# skematikEasyEDA.net
KiCad netlist of a schematic drawn in EasyEDA
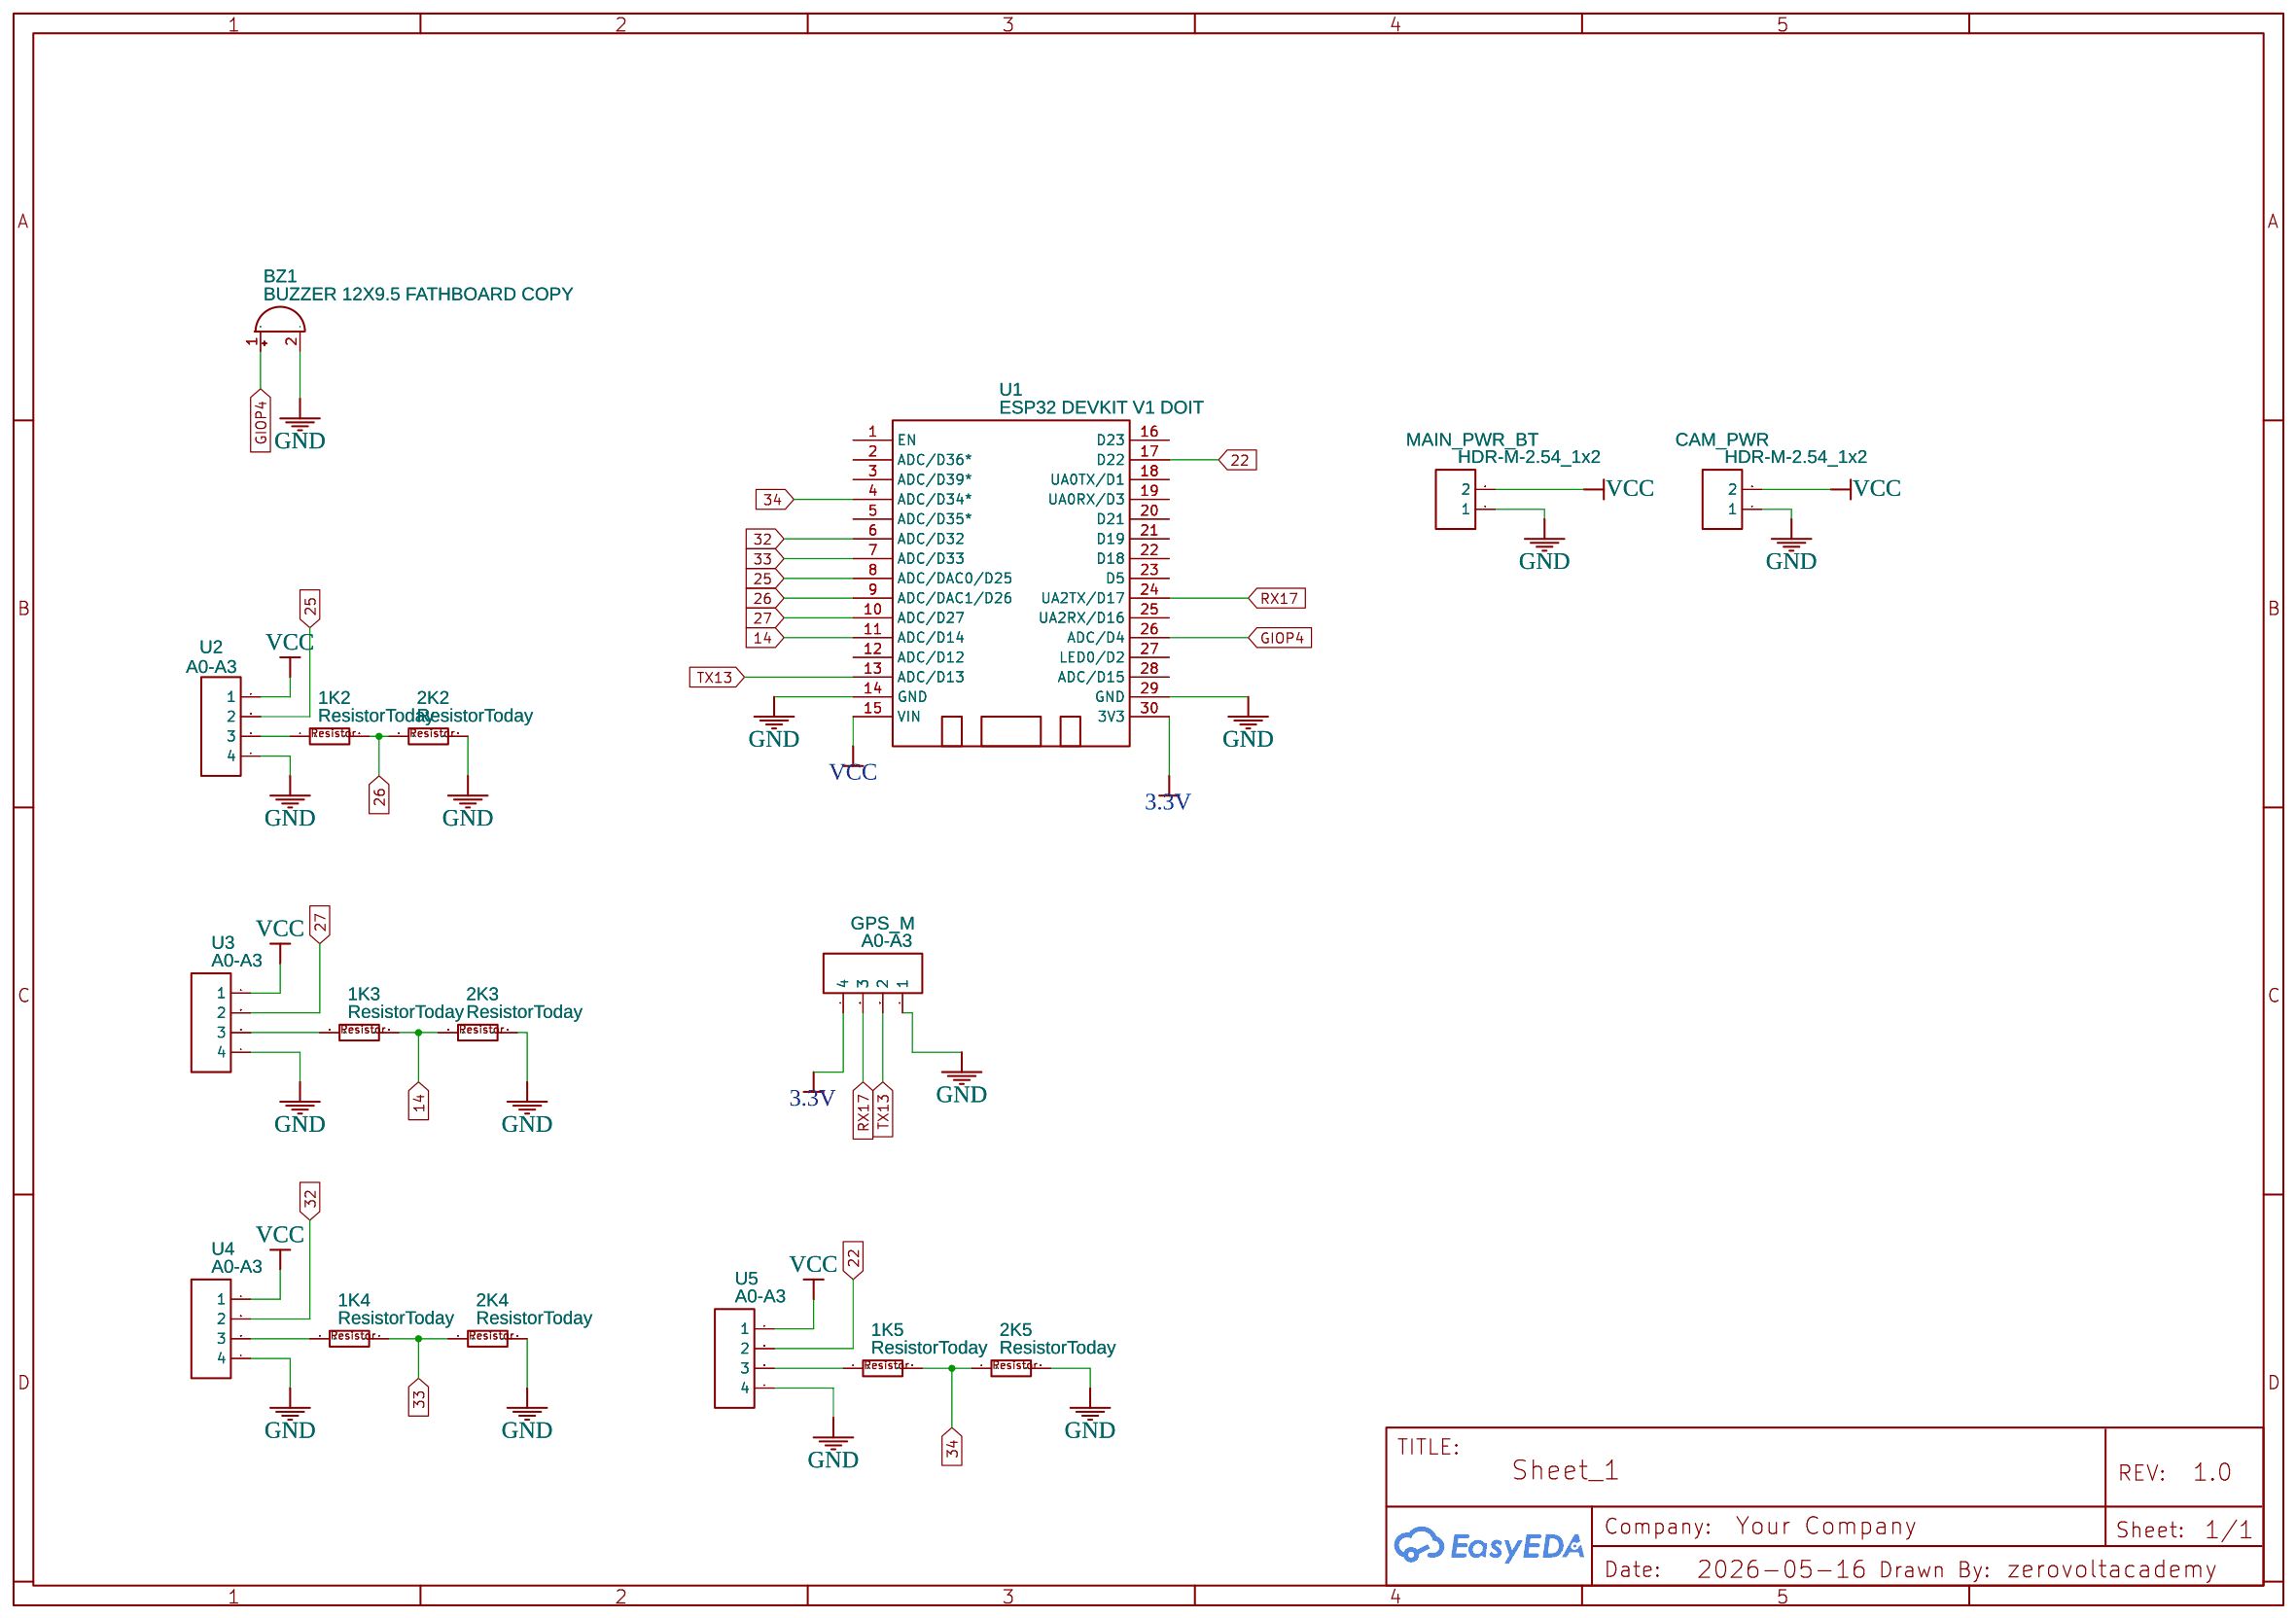
[diagram p0: schematic sheet]

(export (version "E")
  (design (tool "Eeschema 10.0.6"))
  (components
    (comp (ref "1K2")
      (value "ResistorToday")
      (fields (field (name "Manufacturer Part") "EWWR0001J20R0T9"))
      (libsource (lib "") (part "RESISTOR COPY_1"))
    )
    (comp (ref "1K3")
      (value "ResistorToday")
      (fields (field (name "Manufacturer Part") "EWWR0001J20R0T9"))
      (libsource (lib "") (part "RESISTOR COPY_1"))
    )
    (comp (ref "1K4")
      (value "ResistorToday")
      (fields (field (name "Manufacturer Part") "EWWR0001J20R0T9"))
      (libsource (lib "") (part "RESISTOR COPY_1"))
    )
    (comp (ref "1K5")
      (value "ResistorToday")
      (fields (field (name "Manufacturer Part") "EWWR0001J20R0T9"))
      (libsource (lib "") (part "RESISTOR COPY_1"))
    )
    (comp (ref "2K2")
      (value "ResistorToday")
      (fields (field (name "Manufacturer Part") "EWWR0001J20R0T9"))
      (libsource (lib "") (part "RESISTOR COPY"))
    )
    (comp (ref "2K3")
      (value "ResistorToday")
      (fields (field (name "Manufacturer Part") "EWWR0001J20R0T9"))
      (libsource (lib "") (part "RESISTOR COPY"))
    )
    (comp (ref "2K4")
      (value "ResistorToday")
      (fields (field (name "Manufacturer Part") "EWWR0001J20R0T9"))
      (libsource (lib "") (part "RESISTOR COPY"))
    )
    (comp (ref "2K5")
      (value "ResistorToday")
      (fields (field (name "Manufacturer Part") "EWWR0001J20R0T9"))
      (libsource (lib "") (part "RESISTOR COPY"))
    )
    (comp (ref "BZ1")
      (value "BUZZER 12X9.5 FATHBOARD COPY")
      (libsource (lib "") (part "BUZZER 12X9.5 FATHBOARD COPY"))
    )
    (comp (ref "CAM_PWR") (value "HDR-M-2.54_1x2") (libsource (lib "") (part "HDR-M-2.54_1x2_1")))
    (comp (ref "GPS_M")
      (value "A0-A3")
      (fields
        (field (name "Manufacturer Part") "Female headerHDR1X8-2.54")
        (field (name "Manufacturer") "BOOMELE")
      )
      (libsource (lib "") (part "HEADER PAD 2X_1"))
    )
    (comp (ref "MAIN_PWR_BT") (value "HDR-M-2.54_1x2") (libsource (lib "") (part "HDR-M-2.54_1x2")))
    (comp (ref "U1") (value "ESP32 DEVKIT V1 DOIT") (libsource (lib "") (part "ESP32 DEVKIT V1 DOIT")))
    (comp (ref "U2")
      (value "A0-A3")
      (fields
        (field (name "Manufacturer Part") "Female headerHDR1X8-2.54")
        (field (name "Manufacturer") "BOOMELE")
      )
      (libsource (lib "") (part "HEADER PAD 2X"))
    )
    (comp (ref "U3")
      (value "A0-A3")
      (fields
        (field (name "Manufacturer Part") "Female headerHDR1X8-2.54")
        (field (name "Manufacturer") "BOOMELE")
      )
      (libsource (lib "") (part "HEADER PAD 2X"))
    )
    (comp (ref "U4")
      (value "A0-A3")
      (fields
        (field (name "Manufacturer Part") "Female headerHDR1X8-2.54")
        (field (name "Manufacturer") "BOOMELE")
      )
      (libsource (lib "") (part "HEADER PAD 2X"))
    )
    (comp (ref "U5")
      (value "A0-A3")
      (fields
        (field (name "Manufacturer Part") "Female headerHDR1X8-2.54")
        (field (name "Manufacturer") "BOOMELE")
      )
      (libsource (lib "") (part "HEADER PAD 2X"))
    )
  )
  (nets
    (net (code "1") (name "3.3V") (class "Default")
      (node (ref "GPS_M") (pin "4") (pinfunction "4_4") (pintype "unspecified"))
      (node (ref "U1") (pin "30") (pinfunction "3V3_30") (pintype "bidirectional"))
    )
    (net (code "2") (name "14") (class "Default")
      (node (ref "1K3") (pin "2") (pinfunction "2_2") (pintype "unspecified"))
      (node (ref "2K3") (pin "1") (pinfunction "1_1") (pintype "unspecified"))
      (node (ref "U1") (pin "11") (pinfunction "ADC/D14_11") (pintype "bidirectional"))
    )
    (net (code "3") (name "22") (class "Default")
      (node (ref "U1") (pin "17") (pinfunction "D22_17") (pintype "bidirectional"))
      (node (ref "U5") (pin "2") (pinfunction "2_2") (pintype "unspecified"))
    )
    (net (code "4") (name "25") (class "Default")
      (node (ref "U1") (pin "8") (pinfunction "ADC/DAC0/D25_8") (pintype "bidirectional"))
      (node (ref "U2") (pin "2") (pinfunction "2_2") (pintype "unspecified"))
    )
    (net (code "5") (name "26") (class "Default")
      (node (ref "1K2") (pin "2") (pinfunction "2_2") (pintype "unspecified"))
      (node (ref "2K2") (pin "1") (pinfunction "1_1") (pintype "unspecified"))
      (node (ref "U1") (pin "9") (pinfunction "ADC/DAC1/D26_9") (pintype "bidirectional"))
    )
    (net (code "6") (name "27") (class "Default")
      (node (ref "U1") (pin "10") (pinfunction "ADC/D27_10") (pintype "bidirectional"))
      (node (ref "U3") (pin "2") (pinfunction "2_2") (pintype "unspecified"))
    )
    (net (code "7") (name "32") (class "Default")
      (node (ref "U1") (pin "6") (pinfunction "ADC/D32_6") (pintype "bidirectional"))
      (node (ref "U4") (pin "2") (pinfunction "2_2") (pintype "unspecified"))
    )
    (net (code "8") (name "33") (class "Default")
      (node (ref "1K4") (pin "2") (pinfunction "2_2") (pintype "unspecified"))
      (node (ref "2K4") (pin "1") (pinfunction "1_1") (pintype "unspecified"))
      (node (ref "U1") (pin "7") (pinfunction "ADC/D33_7") (pintype "bidirectional"))
    )
    (net (code "9") (name "34") (class "Default")
      (node (ref "1K5") (pin "2") (pinfunction "2_2") (pintype "unspecified"))
      (node (ref "2K5") (pin "1") (pinfunction "1_1") (pintype "unspecified"))
      (node (ref "U1") (pin "4") (pinfunction "ADC/D34*_4") (pintype "input"))
    )
    (net (code "10") (name "GIOP4") (class "Default")
      (node (ref "BZ1") (pin "1") (pinfunction "+_1") (pintype "unspecified"))
      (node (ref "U1") (pin "26") (pinfunction "ADC/D4_26") (pintype "bidirectional"))
    )
    (net (code "11") (name "GND") (class "Default")
      (node (ref "2K2") (pin "2") (pinfunction "2_2") (pintype "unspecified"))
      (node (ref "2K3") (pin "2") (pinfunction "2_2") (pintype "unspecified"))
      (node (ref "2K4") (pin "2") (pinfunction "2_2") (pintype "unspecified"))
      (node (ref "2K5") (pin "2") (pinfunction "2_2") (pintype "unspecified"))
      (node (ref "BZ1") (pin "2") (pinfunction "-_2") (pintype "unspecified"))
      (node (ref "CAM_PWR") (pin "1") (pinfunction "1_1") (pintype "unspecified"))
      (node (ref "GPS_M") (pin "1") (pinfunction "1_1") (pintype "unspecified"))
      (node (ref "MAIN_PWR_BT") (pin "1") (pinfunction "1_1") (pintype "unspecified"))
      (node (ref "U1") (pin "14") (pinfunction "GND_14") (pintype "bidirectional"))
      (node (ref "U1") (pin "29") (pinfunction "GND_29") (pintype "bidirectional"))
      (node (ref "U2") (pin "4") (pinfunction "4_4") (pintype "unspecified"))
      (node (ref "U3") (pin "4") (pinfunction "4_4") (pintype "unspecified"))
      (node (ref "U4") (pin "4") (pinfunction "4_4") (pintype "unspecified"))
      (node (ref "U5") (pin "4") (pinfunction "4_4") (pintype "unspecified"))
    )
    (net (code "12") (name "Net-(1K2-Pad1)") (class "Default")
      (node (ref "1K2") (pin "1") (pinfunction "1_1") (pintype "unspecified"))
      (node (ref "U2") (pin "3") (pinfunction "3_3") (pintype "unspecified"))
    )
    (net (code "13") (name "Net-(1K3-Pad1)") (class "Default")
      (node (ref "1K3") (pin "1") (pinfunction "1_1") (pintype "unspecified"))
      (node (ref "U3") (pin "3") (pinfunction "3_3") (pintype "unspecified"))
    )
    (net (code "14") (name "Net-(1K4-Pad1)") (class "Default")
      (node (ref "1K4") (pin "1") (pinfunction "1_1") (pintype "unspecified"))
      (node (ref "U4") (pin "3") (pinfunction "3_3") (pintype "unspecified"))
    )
    (net (code "15") (name "Net-(1K5-Pad1)") (class "Default")
      (node (ref "1K5") (pin "1") (pinfunction "1_1") (pintype "unspecified"))
      (node (ref "U5") (pin "3") (pinfunction "3_3") (pintype "unspecified"))
    )
    (net (code "16") (name "RX17") (class "Default")
      (node (ref "GPS_M") (pin "3") (pinfunction "3_3") (pintype "unspecified"))
      (node (ref "U1") (pin "24") (pinfunction "UA2TX/D17_24") (pintype "bidirectional"))
    )
    (net (code "17") (name "TX13") (class "Default")
      (node (ref "GPS_M") (pin "2") (pinfunction "2_2") (pintype "unspecified"))
      (node (ref "U1") (pin "13") (pinfunction "ADC/D13_13") (pintype "bidirectional"))
    )
    (net (code "18") (name "VCC") (class "Default")
      (node (ref "CAM_PWR") (pin "2") (pinfunction "2_2") (pintype "unspecified"))
      (node (ref "MAIN_PWR_BT") (pin "2") (pinfunction "2_2") (pintype "unspecified"))
      (node (ref "U1") (pin "15") (pinfunction "VIN_15") (pintype "input"))
      (node (ref "U2") (pin "1") (pinfunction "1_1") (pintype "unspecified"))
      (node (ref "U3") (pin "1") (pinfunction "1_1") (pintype "unspecified"))
      (node (ref "U4") (pin "1") (pinfunction "1_1") (pintype "unspecified"))
      (node (ref "U5") (pin "1") (pinfunction "1_1") (pintype "unspecified"))
    )
    (net (code "19") (name "unconnected-(U1-ADC{slash}D12-Pad12)") (class "Default")
      (node (ref "U1") (pin "12") (pinfunction "ADC/D12_12") (pintype "bidirectional"))
    )
    (net (code "20") (name "unconnected-(U1-ADC{slash}D15-Pad28)") (class "Default")
      (node (ref "U1") (pin "28") (pinfunction "ADC/D15_28") (pintype "bidirectional"))
    )
    (net (code "21") (name "unconnected-(U1-ADC{slash}D35*-Pad5)") (class "Default")
      (node (ref "U1") (pin "5") (pinfunction "ADC/D35*_5") (pintype "input"))
    )
    (net (code "22") (name "unconnected-(U1-ADC{slash}D36*-Pad2)") (class "Default")
      (node (ref "U1") (pin "2") (pinfunction "ADC/D36*_2") (pintype "input"))
    )
    (net (code "23") (name "unconnected-(U1-ADC{slash}D39*-Pad3)") (class "Default")
      (node (ref "U1") (pin "3") (pinfunction "ADC/D39*_3") (pintype "input"))
    )
    (net (code "24") (name "unconnected-(U1-D5-Pad23)") (class "Default")
      (node (ref "U1") (pin "23") (pinfunction "D5_23") (pintype "bidirectional"))
    )
    (net (code "25") (name "unconnected-(U1-D18-Pad22)") (class "Default")
      (node (ref "U1") (pin "22") (pinfunction "D18_22") (pintype "bidirectional"))
    )
    (net (code "26") (name "unconnected-(U1-D19-Pad21)") (class "Default")
      (node (ref "U1") (pin "21") (pinfunction "D19_21") (pintype "bidirectional"))
    )
    (net (code "27") (name "unconnected-(U1-D21-Pad20)") (class "Default")
      (node (ref "U1") (pin "20") (pinfunction "D21_20") (pintype "bidirectional"))
    )
    (net (code "28") (name "unconnected-(U1-D23-Pad16)") (class "Default")
      (node (ref "U1") (pin "16") (pinfunction "D23_16") (pintype "bidirectional"))
    )
    (net (code "29") (name "unconnected-(U1-EN-Pad1)") (class "Default")
      (node (ref "U1") (pin "1") (pinfunction "EN_1") (pintype "bidirectional"))
    )
    (net (code "30") (name "unconnected-(U1-LED0{slash}D2-Pad27)") (class "Default")
      (node (ref "U1") (pin "27") (pinfunction "LED0/D2_27") (pintype "bidirectional"))
    )
    (net (code "31") (name "unconnected-(U1-UA0RX{slash}D3-Pad19)") (class "Default")
      (node (ref "U1") (pin "19") (pinfunction "UA0RX/D3_19") (pintype "bidirectional"))
    )
    (net (code "32") (name "unconnected-(U1-UA0TX{slash}D1-Pad18)") (class "Default")
      (node (ref "U1") (pin "18") (pinfunction "UA0TX/D1_18") (pintype "bidirectional"))
    )
    (net (code "33") (name "unconnected-(U1-UA2RX{slash}D16-Pad25)") (class "Default")
      (node (ref "U1") (pin "25") (pinfunction "UA2RX/D16_25") (pintype "bidirectional"))
    )
  )
)
